# tact_sw_breakout.net
KiCad netlist of a schematic drawn in EAGLE
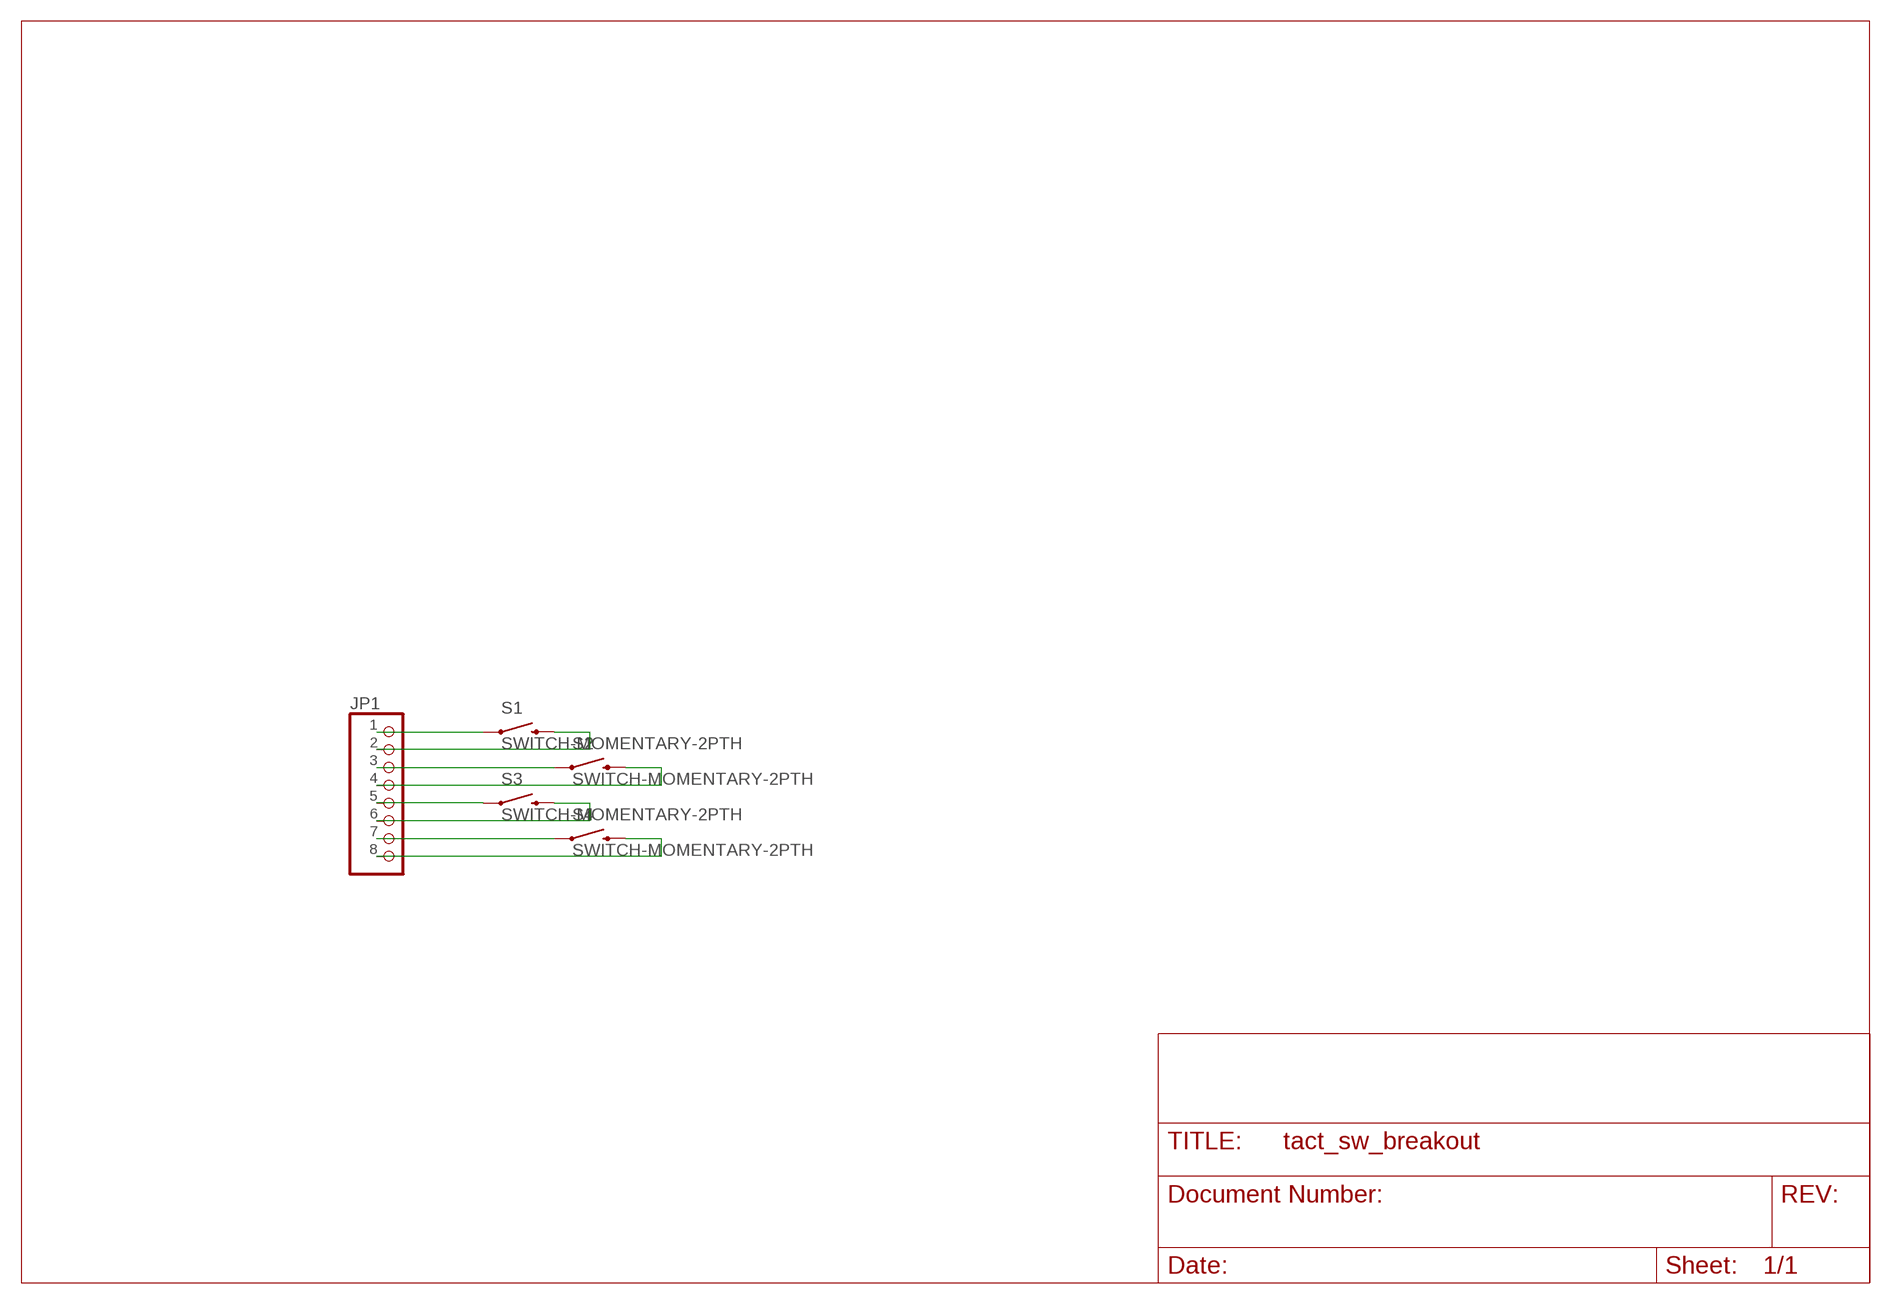
[diagram p0: schematic, sheet 1]

(export (version "E")
  (design (tool "Eeschema 10.0.6"))
  (components
    (comp (ref "JP1")
      (value "PINHD-1X8")
      (footprint "eagle-import:1X08")
      (libsource (lib "eagle-import") (part "PINHD-1X8"))
    )
    (comp (ref "S1")
      (value "SWITCH-MOMENTARY-2PTH")
      (footprint "eagle-import:TACTILE-PTH")
      (libsource (lib "eagle-import") (part "SWITCH-MOMENTARY-2PTH"))
    )
    (comp (ref "S2")
      (value "SWITCH-MOMENTARY-2PTH")
      (footprint "eagle-import:TACTILE-PTH")
      (libsource (lib "eagle-import") (part "SWITCH-MOMENTARY-2PTH"))
    )
    (comp (ref "S3")
      (value "SWITCH-MOMENTARY-2PTH")
      (footprint "eagle-import:TACTILE-PTH")
      (libsource (lib "eagle-import") (part "SWITCH-MOMENTARY-2PTH"))
    )
    (comp (ref "S4")
      (value "SWITCH-MOMENTARY-2PTH")
      (footprint "eagle-import:TACTILE-PTH")
      (libsource (lib "eagle-import") (part "SWITCH-MOMENTARY-2PTH"))
    )
  )
  (nets
    (net (code "1") (name "Net-(JP1-Pad1)") (class "Default")
      (node (ref "JP1") (pin "1") (pinfunction "1_1") (pintype "passive"))
      (node (ref "S1") (pin "1") (pinfunction "1_1") (pintype "passive"))
    )
    (net (code "2") (name "Net-(JP1-Pad3)") (class "Default")
      (node (ref "JP1") (pin "3") (pinfunction "3_3") (pintype "passive"))
      (node (ref "S2") (pin "1") (pinfunction "1_1") (pintype "passive"))
    )
    (net (code "3") (name "Net-(JP1-Pad5)") (class "Default")
      (node (ref "JP1") (pin "5") (pinfunction "5_5") (pintype "passive"))
      (node (ref "S3") (pin "1") (pinfunction "1_1") (pintype "passive"))
    )
    (net (code "4") (name "Net-(JP1-Pad7)") (class "Default")
      (node (ref "JP1") (pin "7") (pinfunction "7_7") (pintype "passive"))
      (node (ref "S4") (pin "1") (pinfunction "1_1") (pintype "passive"))
    )
    (net (code "5") (name "Net-(S1-2)") (class "Default")
      (node (ref "JP1") (pin "2") (pinfunction "2_2") (pintype "passive"))
      (node (ref "S1") (pin "3") (pinfunction "2_3") (pintype "passive"))
    )
    (net (code "6") (name "Net-(S2-2)") (class "Default")
      (node (ref "JP1") (pin "4") (pinfunction "4_4") (pintype "passive"))
      (node (ref "S2") (pin "3") (pinfunction "2_3") (pintype "passive"))
    )
    (net (code "7") (name "Net-(S3-2)") (class "Default")
      (node (ref "JP1") (pin "6") (pinfunction "6_6") (pintype "passive"))
      (node (ref "S3") (pin "3") (pinfunction "2_3") (pintype "passive"))
    )
    (net (code "8") (name "Net-(S4-2)") (class "Default")
      (node (ref "JP1") (pin "8") (pinfunction "8_8") (pintype "passive"))
      (node (ref "S4") (pin "3") (pinfunction "2_3") (pintype "passive"))
    )
  )
)
